# ST_LINK.net
KiCad netlist of a schematic drawn in Altium Designer
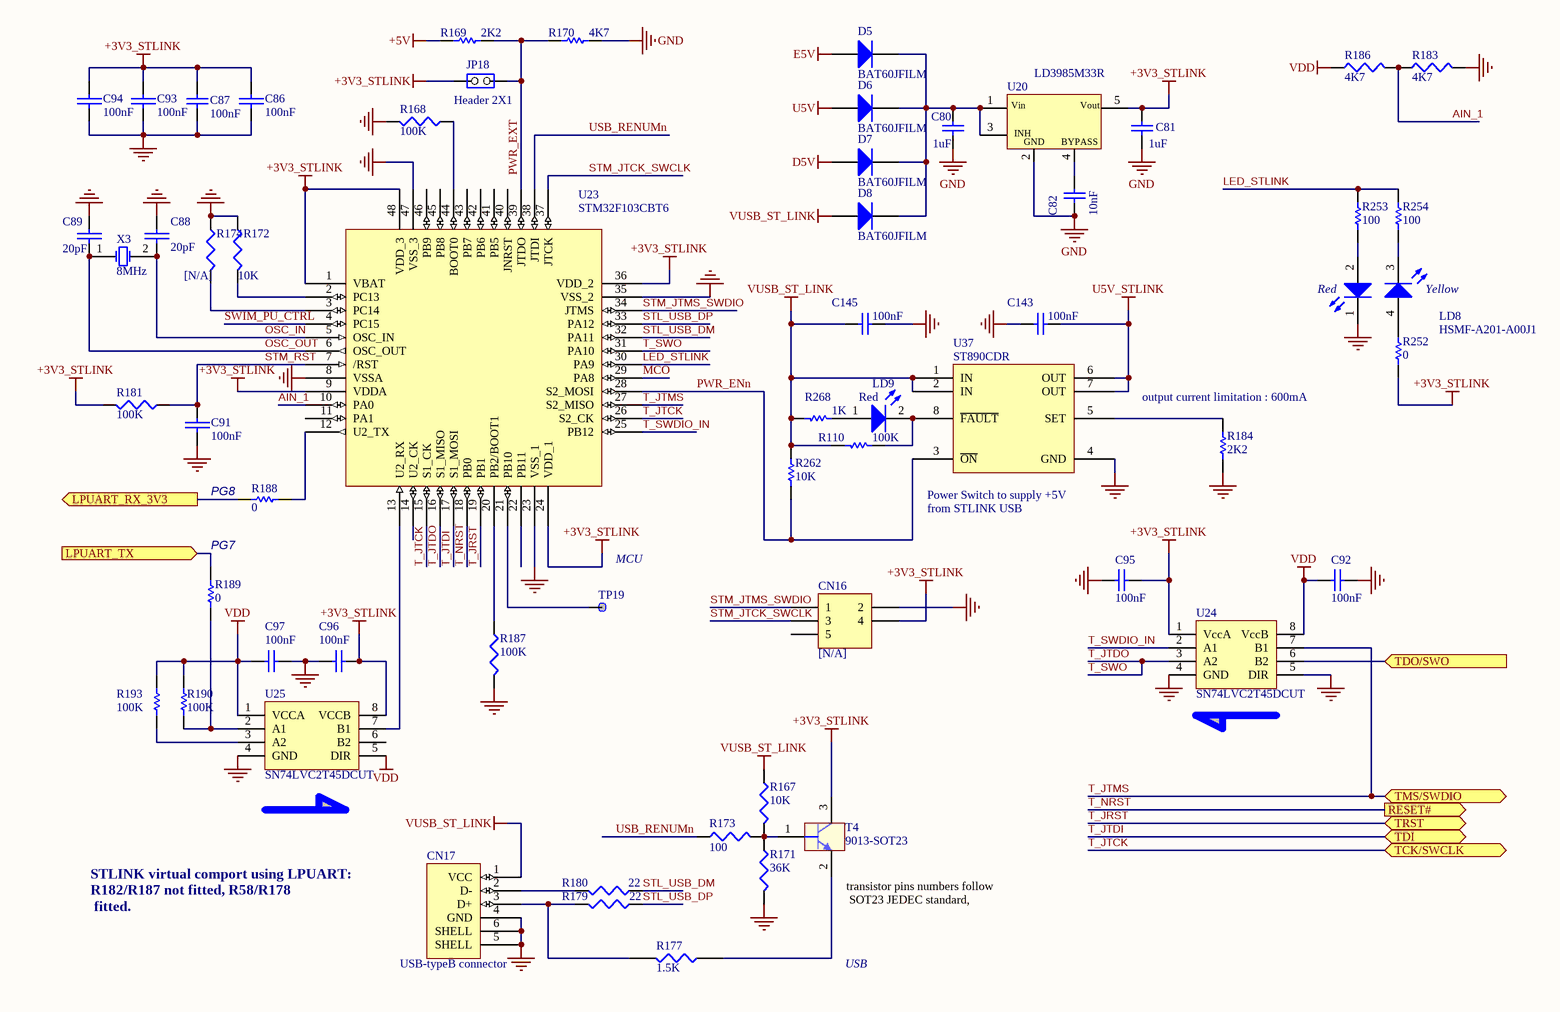
[diagram p0: ST_LINK.SCHDOC]

(export (version "E")
  (design (tool "Eeschema 10.0.6"))
  (components
    (comp (ref "C80")
      (value "1uF")
      (footprint "0603C")
      (description "Capacitor")
      (fields (field (name "PUBLISHER") "Altium Limited"))
      (libsource (lib "Miscellaneous Devices") (part "CAP"))
    )
    (comp (ref "C81")
      (value "1uF")
      (footprint "0603C")
      (description "Capacitor")
      (fields (field (name "PUBLISHER") "Altium Limited"))
      (libsource (lib "Miscellaneous Devices") (part "CAP"))
    )
    (comp (ref "C82")
      (value "10nF")
      (footprint "0402C")
      (description "Capacitor")
      (fields (field (name "PUBLISHER") "Altium Limited"))
      (libsource (lib "Miscellaneous Devices") (part "Cap"))
    )
    (comp (ref "C86") (value "100nF") (footprint "0402C") (libsource (lib "*") (part "CAP")))
    (comp (ref "C87")
      (value "100nF")
      (footprint "0402C")
      (description "Capacitor")
      (fields (field (name "PUBLISHER") "Altium Limited"))
      (libsource (lib "*") (part "Cap"))
    )
    (comp (ref "C88")
      (value "20pF")
      (footprint "0402R")
      (description "Capacitor")
      (libsource (lib "") (part "CAP_1"))
    )
    (comp (ref "C89")
      (value "20pF")
      (footprint "0402R")
      (description "Capacitor")
      (libsource (lib "") (part "CAP_1"))
    )
    (comp (ref "C91") (value "100nF") (footprint "0402C") (libsource (lib "*") (part "CAP")))
    (comp (ref "C92")
      (value "100nF")
      (footprint "0402C")
      (description "Capacitor")
      (fields (field (name "PUBLISHER") "Altium Limited"))
      (libsource (lib "Miscellaneous Devices") (part "CAP"))
    )
    (comp (ref "C93") (value "100nF") (footprint "0402C") (libsource (lib "*") (part "CAP")))
    (comp (ref "C94") (value "100nF") (footprint "0402C") (libsource (lib "*") (part "CAP")))
    (comp (ref "C95")
      (value "100nF")
      (footprint "0402C")
      (description "Capacitor")
      (fields (field (name "PUBLISHER") "Altium Limited"))
      (libsource (lib "Miscellaneous Devices") (part "CAP"))
    )
    (comp (ref "C96")
      (value "100nF")
      (footprint "0402C")
      (description "Capacitor")
      (fields (field (name "PUBLISHER") "Altium Limited"))
      (libsource (lib "Miscellaneous Devices") (part "CAP"))
    )
    (comp (ref "C97")
      (value "100nF")
      (footprint "0402C")
      (description "Capacitor")
      (fields (field (name "PUBLISHER") "Altium Limited"))
      (libsource (lib "Miscellaneous Devices") (part "CAP"))
    )
    (comp (ref "C143")
      (value "100nF")
      (footprint "0402C")
      (description "Capacitor 0402 / 0603 / 0805")
      (libsource (lib "MCD_TOOLS") (part "Capacitor_ST"))
    )
    (comp (ref "C145")
      (value "100nF")
      (footprint "0402C")
      (description "Capacitor 0402 / 0603 / 0805")
      (libsource (lib "MCD_TOOLS") (part "Capacitor_ST"))
    )
    (comp (ref "CN16")
      (value "[N/A]")
      (footprint "HDR_2X3-1_2R54-6")
      (description "Header, 3-Pin, Dual row")
      (fields (field (name "PUBLISHER") "Altium Limited"))
      (libsource (lib "Miscellaneous Connectors") (part "Header 3X2"))
    )
    (comp (ref "CN17")
      (value "USB-typeB connector")
      (footprint "USB-B")
      (libsource (lib "MB1070") (part "USB-typeB connector"))
    )
    (comp (ref "D5")
      (value "BAT60JFILM")
      (footprint "SOD-323")
      (description "Default Diode")
      (fields (field (name "PUBLISHER") "Altium Limited"))
      (libsource (lib "MB1144_1") (part "Diode"))
    )
    (comp (ref "D6")
      (value "BAT60JFILM")
      (footprint "SOD-323")
      (description "Default Diode")
      (fields (field (name "PUBLISHER") "Altium Limited"))
      (libsource (lib "MB1144_1") (part "Diode"))
    )
    (comp (ref "D7")
      (value "BAT60JFILM")
      (footprint "SOD-323")
      (description "Default Diode")
      (fields (field (name "PUBLISHER") "Altium Limited"))
      (libsource (lib "MB1144_1") (part "Diode"))
    )
    (comp (ref "D8")
      (value "BAT60JFILM")
      (footprint "SOD-323")
      (description "Default Diode")
      (fields (field (name "PUBLISHER") "Altium Limited"))
      (libsource (lib "MB1144_1") (part "Diode"))
    )
    (comp (ref "JP18") (value "Header 2X1") (footprint "SIP2") (libsource (lib "*") (part "JP2")))
    (comp (ref "LD8")
      (value "HSMF-A201-A00J1")
      (footprint "LED2_3528")
      (libsource (lib "MB819") (part "HSMF-A201-A00J1"))
    )
    (comp (ref "LD9")
      (value "Red")
      (footprint "0603D")
      (description "Typical RED, GREEN, YELLOW, AMBER GaAs LED")
      (fields (field (name "PUBLISHER") "Altium Limited"))
      (libsource (lib "Miscellaneous Devices") (part "LED2"))
    )
    (comp (ref "R110")
      (value "100K")
      (footprint "0402R")
      (description "Resistor")
      (fields (field (name "PUBLISHER") "Altium Limited"))
      (libsource (lib "*") (part "Res1"))
    )
    (comp (ref "R167")
      (value "10K")
      (footprint "0402R")
      (description "Resistor")
      (libsource (lib "*") (part "R"))
    )
    (comp (ref "R168")
      (value "100K")
      (footprint "0402R")
      (description "Resistor")
      (libsource (lib "*") (part "RES1"))
    )
    (comp (ref "R169")
      (value "2K2")
      (footprint "0402R")
      (description "Resistor")
      (fields (field (name "PUBLISHER") "Altium Limited"))
      (libsource (lib "Miscellaneous Devices") (part "res1"))
    )
    (comp (ref "R170")
      (value "4K7")
      (footprint "0402R")
      (description "Resistor")
      (fields (field (name "PUBLISHER") "Altium Limited"))
      (libsource (lib "Miscellaneous Devices") (part "res1"))
    )
    (comp (ref "R171")
      (value "36K")
      (footprint "0402R")
      (description "Resistor")
      (libsource (lib "*") (part "R"))
    )
    (comp (ref "R172")
      (value "10K")
      (footprint "0402R")
      (description "Resistor")
      (libsource (lib "*") (part "R"))
    )
    (comp (ref "R173")
      (value "100")
      (footprint "0402R")
      (description "Resistor")
      (libsource (lib "*") (part "R"))
    )
    (comp (ref "R174") (value "[N/A]") (footprint "0603R") (libsource (lib "*") (part "R")))
    (comp (ref "R177") (value "1.5K") (footprint "0402R") (libsource (lib "") (part "RES1_1")))
    (comp (ref "R179")
      (value "22")
      (footprint "0402R")
      (description "Resistor")
      (libsource (lib "*") (part "RES1"))
    )
    (comp (ref "R180")
      (value "22")
      (footprint "0402R")
      (description "Resistor")
      (libsource (lib "*") (part "RES1"))
    )
    (comp (ref "R181")
      (value "100K")
      (footprint "0402R")
      (description "Resistor")
      (libsource (lib "*") (part "RES1"))
    )
    (comp (ref "R183") (value "4K7") (footprint "0402R") (libsource (lib "*") (part "RES1")))
    (comp (ref "R184")
      (value "2K2")
      (footprint "0402R")
      (description "Resistor")
      (fields (field (name "PUBLISHER") "Altium Limited"))
      (libsource (lib "Miscellaneous Devices") (part "res1"))
    )
    (comp (ref "R186") (value "4K7") (footprint "0402R") (libsource (lib "*") (part "RES1")))
    (comp (ref "R187")
      (value "100K")
      (footprint "0402R")
      (description "Resistor")
      (libsource (lib "*") (part "RES1"))
    )
    (comp (ref "R188")
      (value "0")
      (footprint "0603R")
      (description "Resistor")
      (fields (field (name "PUBLISHER") "Altium Limited"))
      (libsource (lib "Miscellaneous Devices") (part "Res1"))
    )
    (comp (ref "R189")
      (value "0")
      (footprint "0603R")
      (description "Resistor")
      (fields (field (name "PUBLISHER") "Altium Limited"))
      (libsource (lib "Miscellaneous Devices") (part "Res1"))
    )
    (comp (ref "R190")
      (value "100K")
      (footprint "0402R")
      (description "Resistor")
      (fields (field (name "PUBLISHER") "Altium Limited"))
      (libsource (lib "Miscellaneous Devices") (part "Res1"))
    )
    (comp (ref "R193")
      (value "100K")
      (footprint "0402R")
      (description "Resistor")
      (fields (field (name "PUBLISHER") "Altium Limited"))
      (libsource (lib "Miscellaneous Devices") (part "Res1"))
    )
    (comp (ref "R252")
      (value "0")
      (footprint "0603R")
      (description "Resistor")
      (fields (field (name "PUBLISHER") "Altium Limited"))
      (libsource (lib "Miscellaneous Devices") (part "Res1"))
    )
    (comp (ref "R253")
      (value "100")
      (footprint "0402R")
      (description "Resistor")
      (fields (field (name "PUBLISHER") "Altium Limited"))
      (libsource (lib "Miscellaneous Devices") (part "Res1"))
    )
    (comp (ref "R254")
      (value "100")
      (footprint "0402R")
      (description "Resistor")
      (fields (field (name "PUBLISHER") "Altium Limited"))
      (libsource (lib "Miscellaneous Devices") (part "Res1"))
    )
    (comp (ref "R262")
      (value "10K")
      (footprint "0402R")
      (description "Resistor 0402 or 0603 or 0805")
      (libsource (lib "MCD_TOOLS") (part "Resistor_ST"))
    )
    (comp (ref "R268")
      (value "1K")
      (footprint "0402R")
      (description "Resistor")
      (fields (field (name "PUBLISHER") "Altium Limited"))
      (libsource (lib "*") (part "Res1"))
    )
    (comp (ref "T4")
      (value "9013-SOT23")
      (footprint "SOT-23")
      (description "NPN Bipolar Transistor, SOT-23 Footprint")
      (libsource (lib "MCD_TOOLS") (part "9013-SOT23"))
    )
    (comp (ref "TP19") (value "[N/A]") (footprint "TP_C79") (libsource (lib "MB1144") (part "TP")))
    (comp (ref "U20")
      (value "LD3985M33R")
      (footprint "SOT23-5")
      (description "Ultra low drop-low noise BiCMOS voltage, regulators low ESR capacitors compatible")
      (libsource (lib "MCD_TOOLS") (part "LD3985M33R"))
    )
    (comp (ref "U23")
      (value "STM32F103CBT6")
      (footprint "LQFP48_0R5_9X9")
      (libsource (lib "*") (part "STM32F10x(48pin)"))
    )
    (comp (ref "U24")
      (value "SN74LVC2T45DCUT")
      (footprint "USOP8_0R5_2X3R1")
      (libsource (lib "STLINK") (part "SN74LVC2T45DCUT"))
    )
    (comp (ref "U25")
      (value "SN74LVC2T45DCUT")
      (footprint "USOP8_0R5_2X3R1")
      (libsource (lib "MB818") (part "SN74LVC2T45DCUT"))
    )
    (comp (ref "U37")
      (value "ST890CDR")
      (footprint "SOIC8_1R27_4R9X6")
      (libsource (lib "MB1167") (part "ST890CDR"))
    )
    (comp (ref "X3")
      (value "8MHz")
      (footprint "XTAL_2SM_12R7X4R7")
      (description "Crystal Oscillator")
      (fields (field (name "PUBLISHER") "Altium Limited"))
      (libsource (lib "*") (part "XTAL"))
    )
  )
  (nets
    (net (code "1") (name "+3V3_STLINK") (class "Default")
      (node (ref "C81") (pin "1") (pinfunction "1_1") (pintype "passive"))
      (node (ref "C86") (pin "2") (pinfunction "2_2") (pintype "passive"))
      (node (ref "C87") (pin "1") (pinfunction "1_1") (pintype "passive"))
      (node (ref "C93") (pin "2") (pinfunction "2_2") (pintype "passive"))
      (node (ref "C94") (pin "2") (pinfunction "2_2") (pintype "passive"))
      (node (ref "C95") (pin "2") (pinfunction "2_2") (pintype "passive"))
      (node (ref "C96") (pin "1") (pinfunction "1_1") (pintype "passive"))
      (node (ref "CN16") (pin "4") (pinfunction "4_4") (pintype "passive"))
      (node (ref "JP18") (pin "1") (pinfunction "COMMON_1") (pintype "passive"))
      (node (ref "R181") (pin "2") (pinfunction "2_2") (pintype "passive"))
      (node (ref "R252") (pin "2") (pinfunction "2_2") (pintype "passive"))
      (node (ref "T4") (pin "3") (pinfunction "C_3") (pintype "passive"))
      (node (ref "U20") (pin "5") (pinfunction "Vout_5") (pintype "passive"))
      (node (ref "U23") (pin "1") (pinfunction "VBAT_1") (pintype "power_in"))
      (node (ref "U23") (pin "24") (pinfunction "VDD_1_24") (pintype "power_in"))
      (node (ref "U23") (pin "36") (pinfunction "VDD_2_36") (pintype "power_in"))
      (node (ref "U23") (pin "48") (pinfunction "VDD_3_48") (pintype "power_in"))
      (node (ref "U23") (pin "9") (pinfunction "VDDA_9") (pintype "power_in"))
      (node (ref "U24") (pin "1") (pinfunction "VccA_1") (pintype "passive"))
      (node (ref "U25") (pin "8") (pinfunction "VCCB_8") (pintype "passive"))
    )
    (net (code "2") (name "+5V") (class "Default")
      (node (ref "R169") (pin "2") (pinfunction "2_2") (pintype "passive"))
    )
    (net (code "3") (name "/AIN_1") (class "Default")
      (node (ref "R183") (pin "1") (pinfunction "1_1") (pintype "passive"))
      (node (ref "R186") (pin "2") (pinfunction "2_2") (pintype "passive"))
      (node (ref "U23") (pin "10") (pinfunction "PA0_10") (pintype "bidirectional"))
    )
    (net (code "4") (name "/LED_STLINK") (class "Default")
      (node (ref "R253") (pin "1") (pinfunction "1_1") (pintype "passive"))
      (node (ref "R254") (pin "1") (pinfunction "1_1") (pintype "passive"))
      (node (ref "U23") (pin "30") (pinfunction "PA9_30") (pintype "bidirectional"))
    )
    (net (code "5") (name "/LPUART_RX_3V3") (class "Default")
      (node (ref "R188") (pin "2") (pinfunction "2_2") (pintype "passive"))
    )
    (net (code "6") (name "/LPUART_TX") (class "Default")
      (node (ref "R189") (pin "1") (pinfunction "1_1") (pintype "passive"))
    )
    (net (code "7") (name "/MCO") (class "Default")
      (node (ref "U23") (pin "29") (pinfunction "PA8_29") (pintype "bidirectional"))
    )
    (net (code "8") (name "/OSC_IN") (class "Default")
      (node (ref "C88") (pin "2") (pinfunction "2_2") (pintype "passive"))
      (node (ref "U23") (pin "5") (pinfunction "OSC_IN_5") (pintype "input"))
      (node (ref "X3") (pin "2") (pinfunction "OSC2_2") (pintype "passive"))
    )
    (net (code "9") (name "/OSC_OUT") (class "Default")
      (node (ref "C89") (pin "2") (pinfunction "2_2") (pintype "passive"))
      (node (ref "U23") (pin "6") (pinfunction "OSC_OUT_6") (pintype "output"))
      (node (ref "X3") (pin "1") (pinfunction "OSC1_1") (pintype "passive"))
    )
    (net (code "10") (name "/PWR_ENn") (class "Default")
      (node (ref "R262") (pin "1") (pinfunction "1_1") (pintype "passive"))
      (node (ref "U23") (pin "28") (pinfunction "S2_MOSI_28") (pintype "bidirectional"))
      (node (ref "U37") (pin "3") (pinfunction "~{ON}_3") (pintype "passive"))
    )
    (net (code "11") (name "/PWR_EXT") (class "Default")
      (node (ref "JP18") (pin "2") (pinfunction "NO_2") (pintype "passive"))
      (node (ref "R169") (pin "1") (pinfunction "1_1") (pintype "passive"))
      (node (ref "R170") (pin "2") (pinfunction "2_2") (pintype "passive"))
      (node (ref "U23") (pin "39") (pinfunction "JTDO_39") (pintype "bidirectional"))
    )
    (net (code "12") (name "/STL_USB_DM") (class "Default")
      (node (ref "R180") (pin "1") (pinfunction "1_1") (pintype "passive"))
      (node (ref "U23") (pin "32") (pinfunction "PA11_32") (pintype "bidirectional"))
    )
    (net (code "13") (name "/STL_USB_DP") (class "Default")
      (node (ref "R179") (pin "1") (pinfunction "1_1") (pintype "passive"))
      (node (ref "U23") (pin "33") (pinfunction "PA12_33") (pintype "bidirectional"))
    )
    (net (code "14") (name "/STM_JTCK_SWCLK") (class "Default")
      (node (ref "CN16") (pin "3") (pinfunction "3_3") (pintype "passive"))
      (node (ref "U23") (pin "37") (pinfunction "JTCK_37") (pintype "bidirectional"))
    )
    (net (code "15") (name "/STM_JTMS_SWDIO") (class "Default")
      (node (ref "CN16") (pin "1") (pinfunction "1_1") (pintype "passive"))
      (node (ref "U23") (pin "34") (pinfunction "JTMS_34") (pintype "bidirectional"))
    )
    (net (code "16") (name "/STM_RST") (class "Default")
      (node (ref "C91") (pin "2") (pinfunction "2_2") (pintype "passive"))
      (node (ref "R181") (pin "1") (pinfunction "1_1") (pintype "passive"))
      (node (ref "U23") (pin "7") (pinfunction "/RST_7") (pintype "input"))
    )
    (net (code "17") (name "/SWIM_PU_CTRL") (class "Default")
      (node (ref "U23") (pin "4") (pinfunction "PC15_4") (pintype "bidirectional"))
    )
    (net (code "18") (name "/TDO{slash}SWO") (class "Default")
      (node (ref "U24") (pin "6") (pinfunction "B2_6") (pintype "passive"))
    )
    (net (code "19") (name "/T_JRST") (class "Default")
      (node (ref "U23") (pin "19") (pinfunction "PB1_19") (pintype "bidirectional"))
    )
    (net (code "20") (name "/T_JTCK") (class "Default")
      (node (ref "U23") (pin "15") (pinfunction "S1_CK_15") (pintype "bidirectional"))
      (node (ref "U23") (pin "26") (pinfunction "S2_CK_26") (pintype "bidirectional"))
    )
    (net (code "21") (name "/T_JTDI") (class "Default")
      (node (ref "U23") (pin "17") (pinfunction "S1_MOSI_17") (pintype "bidirectional"))
    )
    (net (code "22") (name "/T_JTDO") (class "Default")
      (node (ref "U23") (pin "16") (pinfunction "S1_MISO_16") (pintype "bidirectional"))
      (node (ref "U23") (pin "31") (pinfunction "PA10_31") (pintype "bidirectional"))
      (node (ref "U24") (pin "3") (pinfunction "A2_3") (pintype "passive"))
    )
    (net (code "23") (name "/T_JTMS") (class "Default")
      (node (ref "U23") (pin "27") (pinfunction "S2_MISO_27") (pintype "bidirectional"))
      (node (ref "U24") (pin "7") (pinfunction "B1_7") (pintype "passive"))
    )
    (net (code "24") (name "/T_NRST") (class "Default")
      (node (ref "U23") (pin "18") (pinfunction "PB0_18") (pintype "bidirectional"))
    )
    (net (code "25") (name "/T_SWDIO_IN") (class "Default")
      (node (ref "U23") (pin "25") (pinfunction "PB12_25") (pintype "bidirectional"))
      (node (ref "U24") (pin "2") (pinfunction "A1_2") (pintype "passive"))
    )
    (net (code "26") (name "/USB_RENUMn") (class "Default")
      (node (ref "R173") (pin "1") (pinfunction "1_1") (pintype "passive"))
      (node (ref "U23") (pin "38") (pinfunction "JTDI_38") (pintype "bidirectional"))
    )
    (net (code "27") (name "D5V") (class "Default")
      (node (ref "D7") (pin "1") (pinfunction "A_1") (pintype "passive"))
    )
    (net (code "28") (name "E5V") (class "Default")
      (node (ref "D5") (pin "1") (pinfunction "A_1") (pintype "passive"))
    )
    (net (code "29") (name "GND") (class "Default")
      (node (ref "C143") (pin "1") (pinfunction "1_1") (pintype "passive"))
      (node (ref "C145") (pin "2") (pinfunction "2_2") (pintype "passive"))
      (node (ref "C80") (pin "2") (pinfunction "2_2") (pintype "passive"))
      (node (ref "C81") (pin "2") (pinfunction "2_2") (pintype "passive"))
      (node (ref "C82") (pin "2") (pinfunction "2_2") (pintype "passive"))
      (node (ref "C86") (pin "1") (pinfunction "1_1") (pintype "passive"))
      (node (ref "C87") (pin "2") (pinfunction "2_2") (pintype "passive"))
      (node (ref "C88") (pin "1") (pinfunction "1_1") (pintype "passive"))
      (node (ref "C89") (pin "1") (pinfunction "1_1") (pintype "passive"))
      (node (ref "C91") (pin "1") (pinfunction "1_1") (pintype "passive"))
      (node (ref "C92") (pin "2") (pinfunction "2_2") (pintype "passive"))
      (node (ref "C93") (pin "1") (pinfunction "1_1") (pintype "passive"))
      (node (ref "C94") (pin "1") (pinfunction "1_1") (pintype "passive"))
      (node (ref "C95") (pin "1") (pinfunction "1_1") (pintype "passive"))
      (node (ref "C96") (pin "2") (pinfunction "2_2") (pintype "passive"))
      (node (ref "C97") (pin "2") (pinfunction "2_2") (pintype "passive"))
      (node (ref "CN16") (pin "2") (pinfunction "2_2") (pintype "passive"))
      (node (ref "CN17") (pin "4") (pinfunction "GND_4") (pintype "passive"))
      (node (ref "CN17") (pin "5") (pinfunction "SHELL_5") (pintype "power_in"))
      (node (ref "CN17") (pin "6") (pinfunction "SHELL_6") (pintype "power_in"))
      (node (ref "LD8") (pin "1") (pinfunction "RED_cathode_1") (pintype "passive"))
      (node (ref "R168") (pin "2") (pinfunction "2_2") (pintype "passive"))
      (node (ref "R170") (pin "1") (pinfunction "1_1") (pintype "passive"))
      (node (ref "R171") (pin "2") (pinfunction "2_2") (pintype "passive"))
      (node (ref "R172") (pin "1") (pinfunction "1_1") (pintype "passive"))
      (node (ref "R174") (pin "1") (pinfunction "1_1") (pintype "passive"))
      (node (ref "R183") (pin "2") (pinfunction "2_2") (pintype "passive"))
      (node (ref "R184") (pin "2") (pinfunction "2_2") (pintype "passive"))
      (node (ref "R187") (pin "2") (pinfunction "2_2") (pintype "passive"))
      (node (ref "U20") (pin "2") (pinfunction "GND_2") (pintype "passive"))
      (node (ref "U23") (pin "23") (pinfunction "VSS_1_23") (pintype "passive"))
      (node (ref "U23") (pin "35") (pinfunction "VSS_2_35") (pintype "passive"))
      (node (ref "U23") (pin "47") (pinfunction "VSS_3_47") (pintype "passive"))
      (node (ref "U23") (pin "8") (pinfunction "VSSA_8") (pintype "passive"))
      (node (ref "U24") (pin "4") (pinfunction "GND_4") (pintype "passive"))
      (node (ref "U24") (pin "5") (pinfunction "DIR_5") (pintype "passive"))
      (node (ref "U25") (pin "4") (pinfunction "GND_4") (pintype "passive"))
      (node (ref "U37") (pin "4") (pinfunction "GND_4") (pintype "passive"))
    )
    (net (code "30") (name "Net-(CN17-D+)") (class "Default")
      (node (ref "CN17") (pin "3") (pinfunction "D+_3") (pintype "bidirectional"))
      (node (ref "R177") (pin "2") (pinfunction "2_2") (pintype "passive"))
      (node (ref "R179") (pin "2") (pinfunction "2_2") (pintype "passive"))
    )
    (net (code "31") (name "Net-(CN17-D-)") (class "Default")
      (node (ref "CN17") (pin "2") (pinfunction "D-_2") (pintype "bidirectional"))
      (node (ref "R180") (pin "2") (pinfunction "2_2") (pintype "passive"))
    )
    (net (code "32") (name "Net-(D5-K)") (class "Default")
      (node (ref "C80") (pin "1") (pinfunction "1_1") (pintype "passive"))
      (node (ref "D5") (pin "2") (pinfunction "K_2") (pintype "passive"))
      (node (ref "D6") (pin "2") (pinfunction "K_2") (pintype "passive"))
      (node (ref "D7") (pin "2") (pinfunction "K_2") (pintype "passive"))
      (node (ref "D8") (pin "2") (pinfunction "K_2") (pintype "passive"))
      (node (ref "U20") (pin "1") (pinfunction "Vin_1") (pintype "passive"))
      (node (ref "U20") (pin "3") (pinfunction "CE_3") (pintype "passive"))
    )
    (net (code "33") (name "Net-(LD8-Red_anode)") (class "Default")
      (node (ref "LD8") (pin "2") (pinfunction "Red_anode_2") (pintype "passive"))
      (node (ref "R253") (pin "2") (pinfunction "2_2") (pintype "passive"))
    )
    (net (code "34") (name "Net-(LD8-YellowGreen_anode)") (class "Default")
      (node (ref "LD8") (pin "4") (pinfunction "YellowGreen_anode_4") (pintype "passive"))
      (node (ref "R252") (pin "1") (pinfunction "1_1") (pintype "passive"))
    )
    (net (code "35") (name "Net-(LD8-YellowGreen_cathode)") (class "Default")
      (node (ref "LD8") (pin "3") (pinfunction "YellowGreen_cathode_3") (pintype "passive"))
      (node (ref "R254") (pin "2") (pinfunction "2_2") (pintype "passive"))
    )
    (net (code "36") (name "Net-(LD9-A)") (class "Default")
      (node (ref "LD9") (pin "1") (pinfunction "A_1") (pintype "passive"))
      (node (ref "R268") (pin "2") (pinfunction "2_2") (pintype "passive"))
    )
    (net (code "37") (name "Net-(LD9-K)") (class "Default")
      (node (ref "LD9") (pin "2") (pinfunction "K_2") (pintype "passive"))
      (node (ref "R110") (pin "2") (pinfunction "2_2") (pintype "passive"))
      (node (ref "U37") (pin "8") (pinfunction "~{FAULT}_8") (pintype "passive"))
    )
    (net (code "38") (name "Net-(T4-B)") (class "Default")
      (node (ref "R167") (pin "2") (pinfunction "2_2") (pintype "passive"))
      (node (ref "R171") (pin "1") (pinfunction "1_1") (pintype "passive"))
      (node (ref "R173") (pin "2") (pinfunction "2_2") (pintype "passive"))
      (node (ref "T4") (pin "1") (pinfunction "B_1") (pintype "passive"))
    )
    (net (code "39") (name "Net-(T4-E)") (class "Default")
      (node (ref "R177") (pin "1") (pinfunction "1_1") (pintype "passive"))
      (node (ref "T4") (pin "2") (pinfunction "E_2") (pintype "passive"))
    )
    (net (code "40") (name "Net-(U20-BYPASS)") (class "Default")
      (node (ref "C82") (pin "1") (pinfunction "1_1") (pintype "passive"))
      (node (ref "U20") (pin "4") (pinfunction "BYPASS_4") (pintype "passive"))
    )
    (net (code "41") (name "Net-(U23-BOOT0)") (class "Default")
      (node (ref "R168") (pin "1") (pinfunction "1_1") (pintype "passive"))
      (node (ref "U23") (pin "44") (pinfunction "BOOT0_44") (pintype "bidirectional"))
    )
    (net (code "42") (name "Net-(U23-PB2{slash}BOOT1)") (class "Default")
      (node (ref "R187") (pin "1") (pinfunction "1_1") (pintype "passive"))
      (node (ref "U23") (pin "20") (pinfunction "PB2/BOOT1_20") (pintype "passive"))
    )
    (net (code "43") (name "Net-(U23-PB10)") (class "Default")
      (node (ref "TP19") (pin "1") (pinfunction "1_1") (pintype "passive"))
      (node (ref "U23") (pin "21") (pinfunction "PB10_21") (pintype "bidirectional"))
    )
    (net (code "44") (name "Net-(U23-PC13)") (class "Default")
      (node (ref "R172") (pin "2") (pinfunction "2_2") (pintype "passive"))
      (node (ref "U23") (pin "2") (pinfunction "PC13_2") (pintype "bidirectional"))
    )
    (net (code "45") (name "Net-(U23-PC14)") (class "Default")
      (node (ref "R174") (pin "2") (pinfunction "2_2") (pintype "passive"))
      (node (ref "U23") (pin "3") (pinfunction "PC14_3") (pintype "bidirectional"))
    )
    (net (code "46") (name "Net-(U23-U2_RX)") (class "Default")
      (node (ref "U23") (pin "13") (pinfunction "U2_RX_13") (pintype "input"))
      (node (ref "U25") (pin "7") (pinfunction "B1_7") (pintype "passive"))
    )
    (net (code "47") (name "Net-(U23-U2_TX)") (class "Default")
      (node (ref "R188") (pin "1") (pinfunction "1_1") (pintype "passive"))
      (node (ref "U23") (pin "12") (pinfunction "U2_TX_12") (pintype "output"))
    )
    (net (code "48") (name "Net-(U25-A1)") (class "Default")
      (node (ref "R189") (pin "2") (pinfunction "2_2") (pintype "passive"))
      (node (ref "R190") (pin "2") (pinfunction "2_2") (pintype "passive"))
      (node (ref "U25") (pin "2") (pinfunction "A1_2") (pintype "passive"))
    )
    (net (code "49") (name "Net-(U25-A2)") (class "Default")
      (node (ref "R193") (pin "2") (pinfunction "2_2") (pintype "passive"))
      (node (ref "U25") (pin "3") (pinfunction "A2_3") (pintype "passive"))
    )
    (net (code "50") (name "Net-(U37-SET)") (class "Default")
      (node (ref "R184") (pin "1") (pinfunction "1_1") (pintype "passive"))
      (node (ref "U37") (pin "5") (pinfunction "SET_5") (pintype "passive"))
    )
    (net (code "51") (name "U5V") (class "Default")
      (node (ref "D6") (pin "1") (pinfunction "A_1") (pintype "passive"))
    )
    (net (code "52") (name "U5V_STLINK") (class "Default")
      (node (ref "C143") (pin "2") (pinfunction "2_2") (pintype "passive"))
      (node (ref "U37") (pin "6") (pinfunction "OUT_6") (pintype "passive"))
      (node (ref "U37") (pin "7") (pinfunction "OUT_7") (pintype "passive"))
    )
    (net (code "53") (name "VDD") (class "Default")
      (node (ref "C92") (pin "1") (pinfunction "1_1") (pintype "passive"))
      (node (ref "C97") (pin "1") (pinfunction "1_1") (pintype "passive"))
      (node (ref "R186") (pin "1") (pinfunction "1_1") (pintype "passive"))
      (node (ref "R190") (pin "1") (pinfunction "1_1") (pintype "passive"))
      (node (ref "R193") (pin "1") (pinfunction "1_1") (pintype "passive"))
      (node (ref "U24") (pin "8") (pinfunction "VccB_8") (pintype "passive"))
      (node (ref "U25") (pin "1") (pinfunction "VCCA_1") (pintype "passive"))
      (node (ref "U25") (pin "5") (pinfunction "DIR_5") (pintype "passive"))
    )
    (net (code "54") (name "VUSB_ST_LINK") (class "Default")
      (node (ref "C145") (pin "1") (pinfunction "1_1") (pintype "passive"))
      (node (ref "CN17") (pin "1") (pinfunction "VCC_1") (pintype "bidirectional"))
      (node (ref "D8") (pin "1") (pinfunction "A_1") (pintype "passive"))
      (node (ref "R110") (pin "1") (pinfunction "1_1") (pintype "passive"))
      (node (ref "R167") (pin "1") (pinfunction "1_1") (pintype "passive"))
      (node (ref "R262") (pin "2") (pinfunction "2_2") (pintype "passive"))
      (node (ref "R268") (pin "1") (pinfunction "1_1") (pintype "passive"))
      (node (ref "U37") (pin "1") (pinfunction "IN_1") (pintype "passive"))
      (node (ref "U37") (pin "2") (pinfunction "IN_2") (pintype "passive"))
    )
    (net (code "55") (name "unconnected-(CN16-Pad5)") (class "Default")
      (node (ref "CN16") (pin "5") (pinfunction "5_5") (pintype "passive"))
    )
    (net (code "56") (name "unconnected-(U23-JNRST-Pad40)") (class "Default")
      (node (ref "U23") (pin "40") (pinfunction "JNRST_40") (pintype "bidirectional"))
    )
    (net (code "57") (name "unconnected-(U23-PA1-Pad11)") (class "Default")
      (node (ref "U23") (pin "11") (pinfunction "PA1_11") (pintype "bidirectional"))
    )
    (net (code "58") (name "unconnected-(U23-PB5-Pad41)") (class "Default")
      (node (ref "U23") (pin "41") (pinfunction "PB5_41") (pintype "bidirectional"))
    )
    (net (code "59") (name "unconnected-(U23-PB6-Pad42)") (class "Default")
      (node (ref "U23") (pin "42") (pinfunction "PB6_42") (pintype "bidirectional"))
    )
    (net (code "60") (name "unconnected-(U23-PB7-Pad43)") (class "Default")
      (node (ref "U23") (pin "43") (pinfunction "PB7_43") (pintype "bidirectional"))
    )
    (net (code "61") (name "unconnected-(U23-PB8-Pad45)") (class "Default")
      (node (ref "U23") (pin "45") (pinfunction "PB8_45") (pintype "bidirectional"))
    )
    (net (code "62") (name "unconnected-(U23-PB9-Pad46)") (class "Default")
      (node (ref "U23") (pin "46") (pinfunction "PB9_46") (pintype "bidirectional"))
    )
    (net (code "63") (name "unconnected-(U23-PB11-Pad22)") (class "Default")
      (node (ref "U23") (pin "22") (pinfunction "PB11_22") (pintype "passive"))
    )
    (net (code "64") (name "unconnected-(U23-U2_CK-Pad14)") (class "Default")
      (node (ref "U23") (pin "14") (pinfunction "U2_CK_14") (pintype "bidirectional"))
    )
    (net (code "65") (name "unconnected-(U25-B2-Pad6)") (class "Default")
      (node (ref "U25") (pin "6") (pinfunction "B2_6") (pintype "passive"))
    )
  )
)
